# 4axis_DRV8818.net
KiCad netlist of a schematic drawn in EAGLE
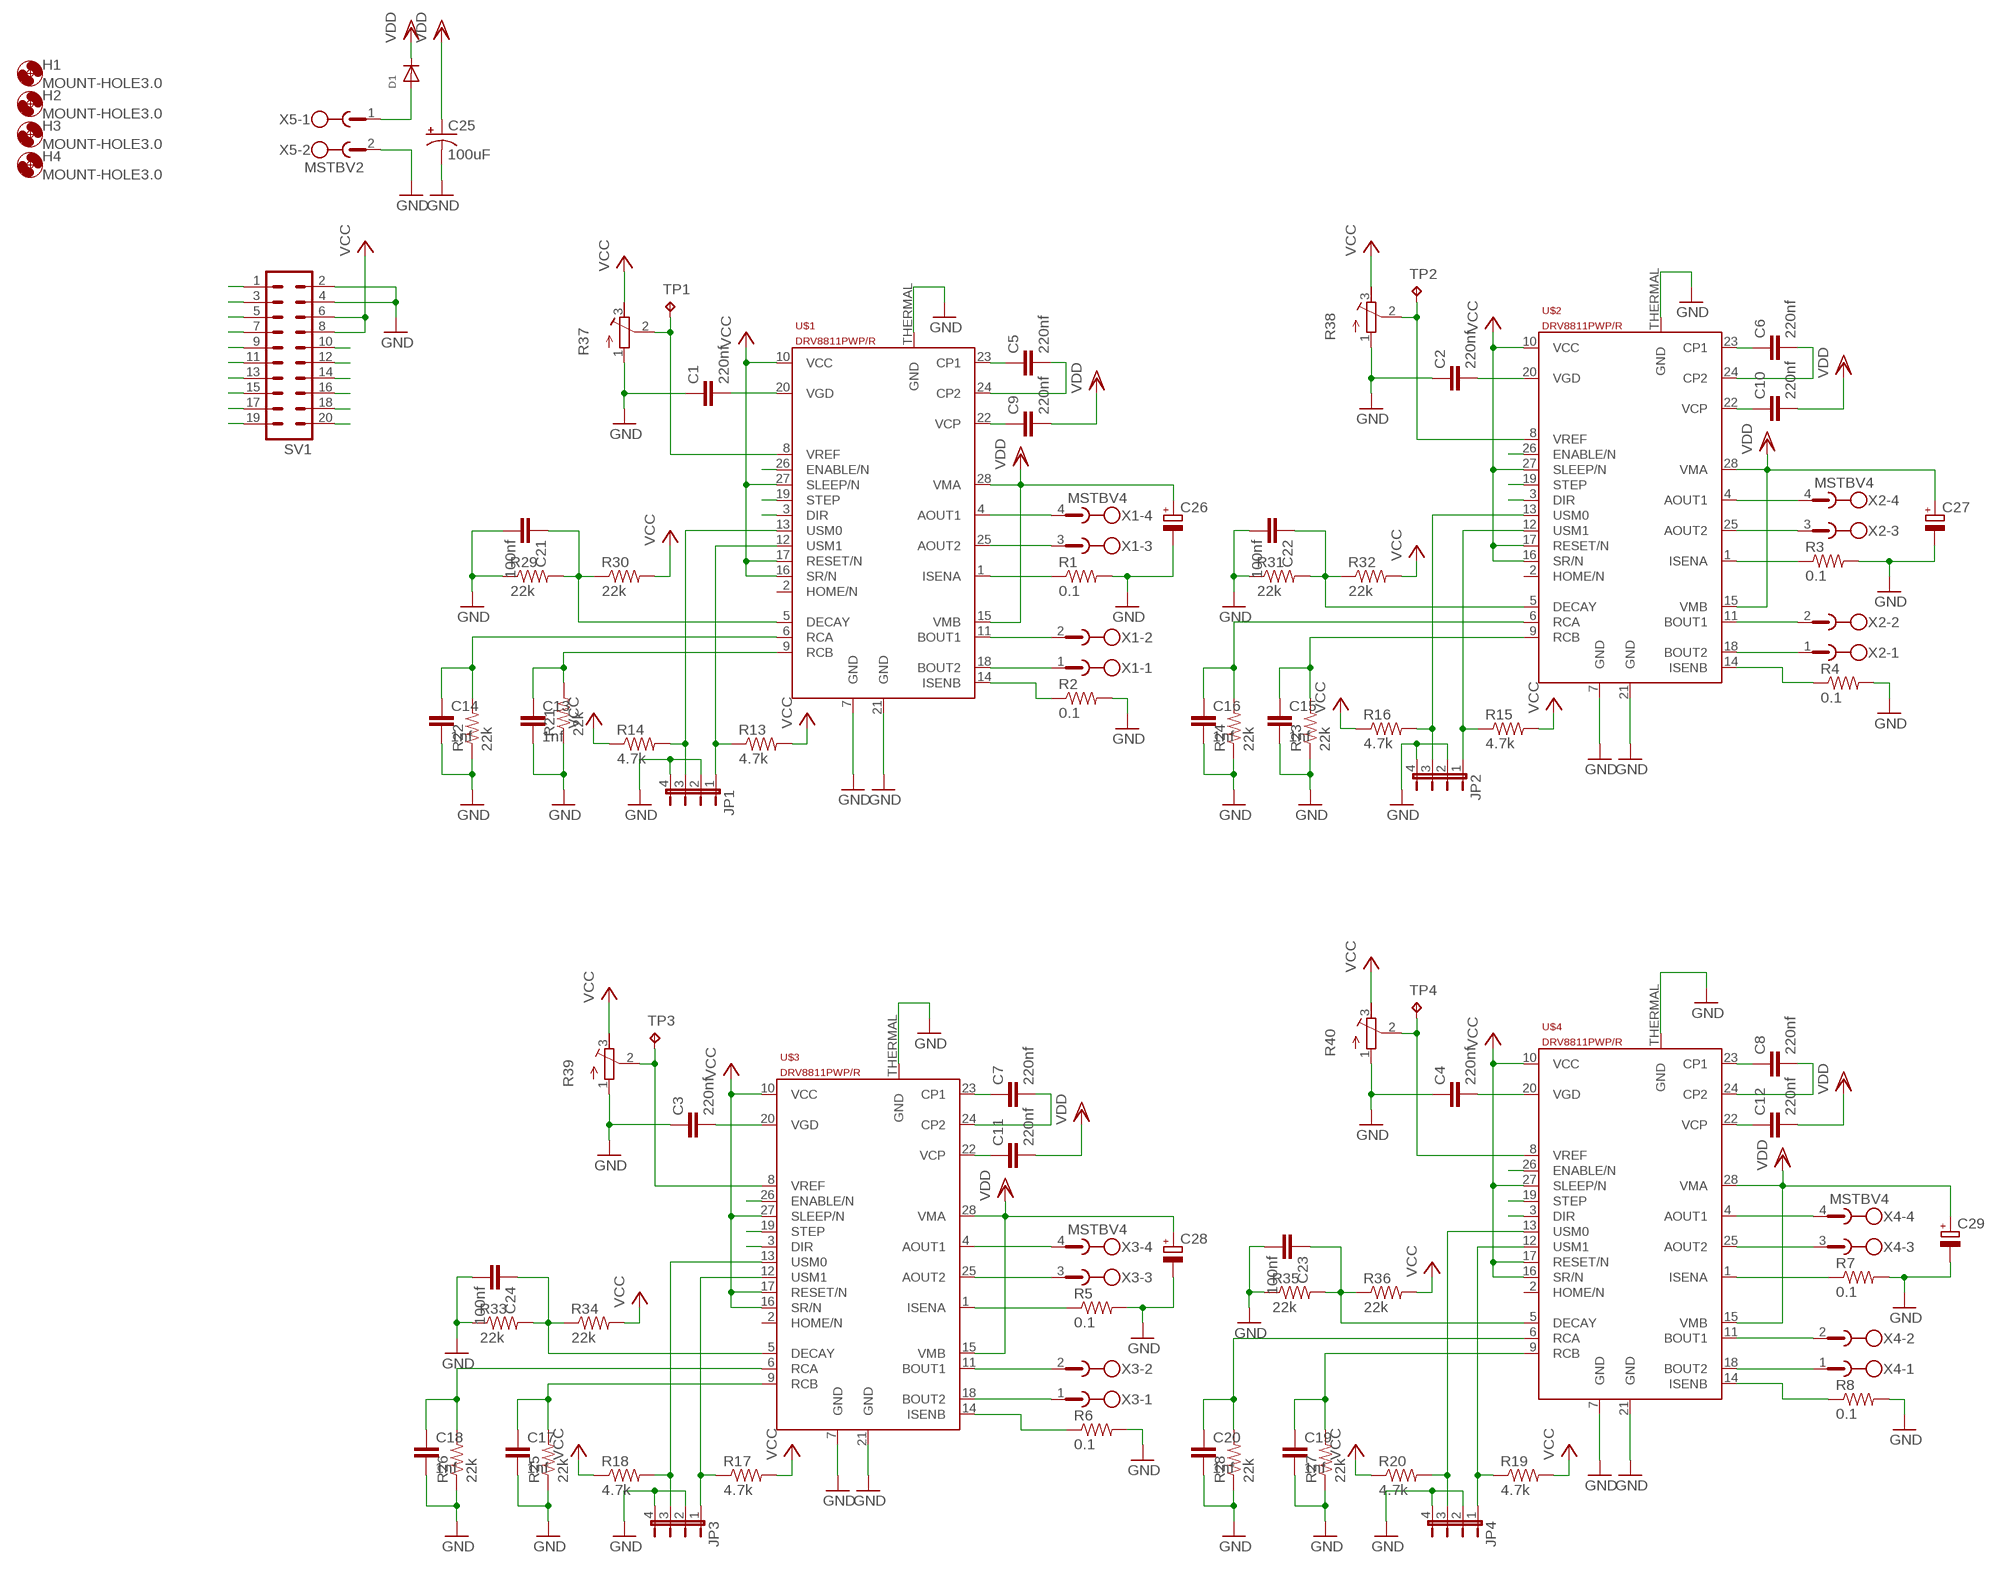
[diagram p0: schematic, sheet 1]

(export (version "E")
  (design (tool "Eeschema 10.0.6"))
  (components
    (comp (ref "C1")
      (value "220nf")
      (footprint "eagle-import:C1206")
      (libsource (lib "eagle-import") (part "C-EUC1206"))
    )
    (comp (ref "C2")
      (value "220nf")
      (footprint "eagle-import:C1206")
      (libsource (lib "eagle-import") (part "C-EUC1206"))
    )
    (comp (ref "C3")
      (value "220nf")
      (footprint "eagle-import:C1206")
      (libsource (lib "eagle-import") (part "C-EUC1206"))
    )
    (comp (ref "C4")
      (value "220nf")
      (footprint "eagle-import:C1206")
      (libsource (lib "eagle-import") (part "C-EUC1206"))
    )
    (comp (ref "C5")
      (value "220nf")
      (footprint "eagle-import:C1206")
      (libsource (lib "eagle-import") (part "C-EUC1206"))
    )
    (comp (ref "C6")
      (value "220nf")
      (footprint "eagle-import:C1206")
      (libsource (lib "eagle-import") (part "C-EUC1206"))
    )
    (comp (ref "C7")
      (value "220nf")
      (footprint "eagle-import:C1206")
      (libsource (lib "eagle-import") (part "C-EUC1206"))
    )
    (comp (ref "C8")
      (value "220nf")
      (footprint "eagle-import:C1206")
      (libsource (lib "eagle-import") (part "C-EUC1206"))
    )
    (comp (ref "C9")
      (value "220nf")
      (footprint "eagle-import:C1206")
      (libsource (lib "eagle-import") (part "C-EUC1206"))
    )
    (comp (ref "C10")
      (value "220nf")
      (footprint "eagle-import:C1206")
      (libsource (lib "eagle-import") (part "C-EUC1206"))
    )
    (comp (ref "C11")
      (value "220nf")
      (footprint "eagle-import:C1206")
      (libsource (lib "eagle-import") (part "C-EUC1206"))
    )
    (comp (ref "C12")
      (value "220nf")
      (footprint "eagle-import:C1206")
      (libsource (lib "eagle-import") (part "C-EUC1206"))
    )
    (comp (ref "C13")
      (value "1nf")
      (footprint "eagle-import:C1206")
      (libsource (lib "eagle-import") (part "C-EUC1206"))
    )
    (comp (ref "C14")
      (value "1nf")
      (footprint "eagle-import:C1206")
      (libsource (lib "eagle-import") (part "C-EUC1206"))
    )
    (comp (ref "C15")
      (value "1nf")
      (footprint "eagle-import:C1206")
      (libsource (lib "eagle-import") (part "C-EUC1206"))
    )
    (comp (ref "C16")
      (value "1nf")
      (footprint "eagle-import:C1206")
      (libsource (lib "eagle-import") (part "C-EUC1206"))
    )
    (comp (ref "C17")
      (value "1nf")
      (footprint "eagle-import:C1206")
      (libsource (lib "eagle-import") (part "C-EUC1206"))
    )
    (comp (ref "C18")
      (value "1nf")
      (footprint "eagle-import:C1206")
      (libsource (lib "eagle-import") (part "C-EUC1206"))
    )
    (comp (ref "C19")
      (value "1nf")
      (footprint "eagle-import:C1206")
      (libsource (lib "eagle-import") (part "C-EUC1206"))
    )
    (comp (ref "C20")
      (value "1nf")
      (footprint "eagle-import:C1206")
      (libsource (lib "eagle-import") (part "C-EUC1206"))
    )
    (comp (ref "C21")
      (value "100nf")
      (footprint "eagle-import:C1206")
      (libsource (lib "eagle-import") (part "C-EUC1206"))
    )
    (comp (ref "C22")
      (value "100nf")
      (footprint "eagle-import:C1206")
      (libsource (lib "eagle-import") (part "C-EUC1206"))
    )
    (comp (ref "C23")
      (value "100nf")
      (footprint "eagle-import:C1206")
      (libsource (lib "eagle-import") (part "C-EUC1206"))
    )
    (comp (ref "C24")
      (value "100nf")
      (footprint "eagle-import:C1206")
      (libsource (lib "eagle-import") (part "C-EUC1206"))
    )
    (comp (ref "C25")
      (value "100uF")
      (footprint "eagle-import:NIC_10X10.5_CAP")
      (libsource (lib "eagle-import") (part "100UF-63V-20%(ELECT)"))
    )
    (comp (ref "C26")
      (value "CPOL-EUD")
      (footprint "eagle-import:PANASONIC_D")
      (libsource (lib "eagle-import") (part "CPOL-EUD"))
    )
    (comp (ref "C27")
      (value "CPOL-EUD")
      (footprint "eagle-import:PANASONIC_D")
      (libsource (lib "eagle-import") (part "CPOL-EUD"))
    )
    (comp (ref "C28")
      (value "CPOL-EUD")
      (footprint "eagle-import:PANASONIC_D")
      (libsource (lib "eagle-import") (part "CPOL-EUD"))
    )
    (comp (ref "C29")
      (value "CPOL-EUD")
      (footprint "eagle-import:PANASONIC_D")
      (libsource (lib "eagle-import") (part "CPOL-EUD"))
    )
    (comp (ref "D1")
      (value "DIODESMA")
      (footprint "eagle-import:SMADIODE")
      (libsource (lib "eagle-import") (part "DIODESMA"))
    )
    (comp (ref "H1")
      (value "MOUNT-HOLE3.0")
      (footprint "eagle-import:3,0")
      (libsource (lib "eagle-import") (part "MOUNT-HOLE3.0"))
    )
    (comp (ref "H2")
      (value "MOUNT-HOLE3.0")
      (footprint "eagle-import:3,0")
      (libsource (lib "eagle-import") (part "MOUNT-HOLE3.0"))
    )
    (comp (ref "H3")
      (value "MOUNT-HOLE3.0")
      (footprint "eagle-import:3,0")
      (libsource (lib "eagle-import") (part "MOUNT-HOLE3.0"))
    )
    (comp (ref "H4")
      (value "MOUNT-HOLE3.0")
      (footprint "eagle-import:3,0")
      (libsource (lib "eagle-import") (part "MOUNT-HOLE3.0"))
    )
    (comp (ref "JP1")
      (value "JP4E")
      (footprint "eagle-import:JP4")
      (libsource (lib "eagle-import") (part "JP4E"))
    )
    (comp (ref "JP2")
      (value "JP4E")
      (footprint "eagle-import:JP4")
      (libsource (lib "eagle-import") (part "JP4E"))
    )
    (comp (ref "JP3")
      (value "JP4E")
      (footprint "eagle-import:JP4")
      (libsource (lib "eagle-import") (part "JP4E"))
    )
    (comp (ref "JP4")
      (value "JP4E")
      (footprint "eagle-import:JP4")
      (libsource (lib "eagle-import") (part "JP4E"))
    )
    (comp (ref "R1")
      (value "0.1")
      (footprint "eagle-import:R2512")
      (libsource (lib "eagle-import") (part "R-US_R2512"))
    )
    (comp (ref "R2")
      (value "0.1")
      (footprint "eagle-import:R2512")
      (libsource (lib "eagle-import") (part "R-US_R2512"))
    )
    (comp (ref "R3")
      (value "0.1")
      (footprint "eagle-import:R2512")
      (libsource (lib "eagle-import") (part "R-US_R2512"))
    )
    (comp (ref "R4")
      (value "0.1")
      (footprint "eagle-import:R2512")
      (libsource (lib "eagle-import") (part "R-US_R2512"))
    )
    (comp (ref "R5")
      (value "0.1")
      (footprint "eagle-import:R2512")
      (libsource (lib "eagle-import") (part "R-US_R2512"))
    )
    (comp (ref "R6")
      (value "0.1")
      (footprint "eagle-import:R2512")
      (libsource (lib "eagle-import") (part "R-US_R2512"))
    )
    (comp (ref "R7")
      (value "0.1")
      (footprint "eagle-import:R2512")
      (libsource (lib "eagle-import") (part "R-US_R2512"))
    )
    (comp (ref "R8")
      (value "0.1")
      (footprint "eagle-import:R2512")
      (libsource (lib "eagle-import") (part "R-US_R2512"))
    )
    (comp (ref "R13")
      (value "4.7k")
      (footprint "eagle-import:R1206")
      (libsource (lib "eagle-import") (part "R-US_R1206"))
    )
    (comp (ref "R14")
      (value "4.7k")
      (footprint "eagle-import:R1206")
      (libsource (lib "eagle-import") (part "R-US_R1206"))
    )
    (comp (ref "R15")
      (value "4.7k")
      (footprint "eagle-import:R1206")
      (libsource (lib "eagle-import") (part "R-US_R1206"))
    )
    (comp (ref "R16")
      (value "4.7k")
      (footprint "eagle-import:R1206")
      (libsource (lib "eagle-import") (part "R-US_R1206"))
    )
    (comp (ref "R17")
      (value "4.7k")
      (footprint "eagle-import:R1206")
      (libsource (lib "eagle-import") (part "R-US_R1206"))
    )
    (comp (ref "R18")
      (value "4.7k")
      (footprint "eagle-import:R1206")
      (libsource (lib "eagle-import") (part "R-US_R1206"))
    )
    (comp (ref "R19")
      (value "4.7k")
      (footprint "eagle-import:R1206")
      (libsource (lib "eagle-import") (part "R-US_R1206"))
    )
    (comp (ref "R20")
      (value "4.7k")
      (footprint "eagle-import:R1206")
      (libsource (lib "eagle-import") (part "R-US_R1206"))
    )
    (comp (ref "R21")
      (value "22k")
      (footprint "eagle-import:R1206")
      (libsource (lib "eagle-import") (part "R-US_R1206"))
    )
    (comp (ref "R22")
      (value "22k")
      (footprint "eagle-import:R1206")
      (libsource (lib "eagle-import") (part "R-US_R1206"))
    )
    (comp (ref "R23")
      (value "22k")
      (footprint "eagle-import:R1206")
      (libsource (lib "eagle-import") (part "R-US_R1206"))
    )
    (comp (ref "R24")
      (value "22k")
      (footprint "eagle-import:R1206")
      (libsource (lib "eagle-import") (part "R-US_R1206"))
    )
    (comp (ref "R25")
      (value "22k")
      (footprint "eagle-import:R1206")
      (libsource (lib "eagle-import") (part "R-US_R1206"))
    )
    (comp (ref "R26")
      (value "22k")
      (footprint "eagle-import:R1206")
      (libsource (lib "eagle-import") (part "R-US_R1206"))
    )
    (comp (ref "R27")
      (value "22k")
      (footprint "eagle-import:R1206")
      (libsource (lib "eagle-import") (part "R-US_R1206"))
    )
    (comp (ref "R28")
      (value "22k")
      (footprint "eagle-import:R1206")
      (libsource (lib "eagle-import") (part "R-US_R1206"))
    )
    (comp (ref "R29")
      (value "22k")
      (footprint "eagle-import:R1206")
      (libsource (lib "eagle-import") (part "R-US_R1206"))
    )
    (comp (ref "R30")
      (value "22k")
      (footprint "eagle-import:R1206")
      (libsource (lib "eagle-import") (part "R-US_R1206"))
    )
    (comp (ref "R31")
      (value "22k")
      (footprint "eagle-import:R1206")
      (libsource (lib "eagle-import") (part "R-US_R1206"))
    )
    (comp (ref "R32")
      (value "22k")
      (footprint "eagle-import:R1206")
      (libsource (lib "eagle-import") (part "R-US_R1206"))
    )
    (comp (ref "R33")
      (value "22k")
      (footprint "eagle-import:R1206")
      (libsource (lib "eagle-import") (part "R-US_R1206"))
    )
    (comp (ref "R34")
      (value "22k")
      (footprint "eagle-import:R1206")
      (libsource (lib "eagle-import") (part "R-US_R1206"))
    )
    (comp (ref "R35")
      (value "22k")
      (footprint "eagle-import:R1206")
      (libsource (lib "eagle-import") (part "R-US_R1206"))
    )
    (comp (ref "R36")
      (value "22k")
      (footprint "eagle-import:R1206")
      (libsource (lib "eagle-import") (part "R-US_R1206"))
    )
    (comp (ref "R37")
      (value "R-TRIMM3103")
      (footprint "eagle-import:RTRIM3103")
      (libsource (lib "eagle-import") (part "R-TRIMM3103"))
    )
    (comp (ref "R38")
      (value "R-TRIMM3103")
      (footprint "eagle-import:RTRIM3103")
      (libsource (lib "eagle-import") (part "R-TRIMM3103"))
    )
    (comp (ref "R39")
      (value "R-TRIMM3103")
      (footprint "eagle-import:RTRIM3103")
      (libsource (lib "eagle-import") (part "R-TRIMM3103"))
    )
    (comp (ref "R40")
      (value "R-TRIMM3103")
      (footprint "eagle-import:RTRIM3103")
      (libsource (lib "eagle-import") (part "R-TRIMM3103"))
    )
    (comp (ref "SV1")
      (value "ML20")
      (footprint "eagle-import:ML20")
      (libsource (lib "eagle-import") (part "ML20"))
    )
    (comp (ref "TP1")
      (value "TPTP20R")
      (footprint "eagle-import:TP20R")
      (libsource (lib "eagle-import") (part "TPTP20R"))
    )
    (comp (ref "TP2")
      (value "TPTP20R")
      (footprint "eagle-import:TP20R")
      (libsource (lib "eagle-import") (part "TPTP20R"))
    )
    (comp (ref "TP3")
      (value "TPTP20R")
      (footprint "eagle-import:TP20R")
      (libsource (lib "eagle-import") (part "TPTP20R"))
    )
    (comp (ref "TP4")
      (value "TPTP20R")
      (footprint "eagle-import:TP20R")
      (libsource (lib "eagle-import") (part "TPTP20R"))
    )
    (comp (ref "U$1")
      (value "DRV8811PWP/R")
      (footprint "eagle-import:HTSSOP28")
      (fields (field (name "MF") "TEXAS INSTRUMENTS"))
      (libsource (lib "eagle-import") (part "DRV8811PWP/R"))
    )
    (comp (ref "U$2")
      (value "DRV8811PWP/R")
      (footprint "eagle-import:HTSSOP28")
      (fields (field (name "MF") "TEXAS INSTRUMENTS"))
      (libsource (lib "eagle-import") (part "DRV8811PWP/R"))
    )
    (comp (ref "U$3")
      (value "DRV8811PWP/R")
      (footprint "eagle-import:HTSSOP28")
      (fields (field (name "MF") "TEXAS INSTRUMENTS"))
      (libsource (lib "eagle-import") (part "DRV8811PWP/R"))
    )
    (comp (ref "U$4")
      (value "DRV8811PWP/R")
      (footprint "eagle-import:HTSSOP28")
      (fields (field (name "MF") "TEXAS INSTRUMENTS"))
      (libsource (lib "eagle-import") (part "DRV8811PWP/R"))
    )
    (comp (ref "X1")
      (value "MSTBV4")
      (footprint "eagle-import:MSTBV4")
      (fields (field (name "MPN") "MSTBV 2,5/4-GF-5.08"))
      (libsource (lib "eagle-import") (part "MSTBV4"))
    )
    (comp (ref "X2")
      (value "MSTBV4")
      (footprint "eagle-import:MSTBV4")
      (fields (field (name "MPN") "MSTBV 2,5/4-GF-5.08"))
      (libsource (lib "eagle-import") (part "MSTBV4"))
    )
    (comp (ref "X3")
      (value "MSTBV4")
      (footprint "eagle-import:MSTBV4")
      (fields (field (name "MPN") "MSTBV 2,5/4-GF-5.08"))
      (libsource (lib "eagle-import") (part "MSTBV4"))
    )
    (comp (ref "X4")
      (value "MSTBV4")
      (footprint "eagle-import:MSTBV4")
      (fields (field (name "MPN") "MSTBV 2,5/4-GF-5.08"))
      (libsource (lib "eagle-import") (part "MSTBV4"))
    )
    (comp (ref "X5")
      (value "MSTBV2")
      (footprint "eagle-import:MSTBV2")
      (fields (field (name "MPN") "MSTBV 2,5/2-GF-5.08"))
      (libsource (lib "eagle-import") (part "MSTBV2"))
    )
  )
  (nets
    (net (code "1") (name "/E-DıR") (class "Default")
      (node (ref "SV1") (pin "14") (pinfunction "14_14") (pintype "passive"))
      (node (ref "U$4") (pin "3") (pinfunction "DIR_3") (pintype "input"))
    )
    (net (code "2") (name "/E-EN") (class "Default")
      (node (ref "SV1") (pin "16") (pinfunction "16_16") (pintype "passive"))
      (node (ref "U$4") (pin "26") (pinfunction "ENABLE/N_26") (pintype "input"))
    )
    (net (code "3") (name "/E-STEP") (class "Default")
      (node (ref "SV1") (pin "12") (pinfunction "12_12") (pintype "passive"))
      (node (ref "U$4") (pin "19") (pinfunction "STEP_19") (pintype "input"))
    )
    (net (code "4") (name "/X-DıR") (class "Default")
      (node (ref "SV1") (pin "3") (pinfunction "3_3") (pintype "passive"))
      (node (ref "U$1") (pin "3") (pinfunction "DIR_3") (pintype "input"))
    )
    (net (code "5") (name "/X-EN") (class "Default")
      (node (ref "SV1") (pin "1") (pinfunction "1_1") (pintype "passive"))
      (node (ref "U$1") (pin "26") (pinfunction "ENABLE/N_26") (pintype "input"))
    )
    (net (code "6") (name "/X-STEP") (class "Default")
      (node (ref "SV1") (pin "5") (pinfunction "5_5") (pintype "passive"))
      (node (ref "U$1") (pin "19") (pinfunction "STEP_19") (pintype "input"))
    )
    (net (code "7") (name "/Y-DıR") (class "Default")
      (node (ref "SV1") (pin "11") (pinfunction "11_11") (pintype "passive"))
      (node (ref "U$2") (pin "3") (pinfunction "DIR_3") (pintype "input"))
    )
    (net (code "8") (name "/Y-EN") (class "Default")
      (node (ref "SV1") (pin "9") (pinfunction "9_9") (pintype "passive"))
      (node (ref "U$2") (pin "26") (pinfunction "ENABLE/N_26") (pintype "input"))
    )
    (net (code "9") (name "/Y-STEP") (class "Default")
      (node (ref "SV1") (pin "13") (pinfunction "13_13") (pintype "passive"))
      (node (ref "U$2") (pin "19") (pinfunction "STEP_19") (pintype "input"))
    )
    (net (code "10") (name "/Z-DıR") (class "Default")
      (node (ref "SV1") (pin "19") (pinfunction "19_19") (pintype "passive"))
      (node (ref "U$3") (pin "3") (pinfunction "DIR_3") (pintype "input"))
    )
    (net (code "11") (name "/Z-EN") (class "Default")
      (node (ref "SV1") (pin "17") (pinfunction "17_17") (pintype "passive"))
      (node (ref "U$3") (pin "26") (pinfunction "ENABLE/N_26") (pintype "input"))
    )
    (net (code "12") (name "/Z-STEP") (class "Default")
      (node (ref "SV1") (pin "20") (pinfunction "20_20") (pintype "passive"))
      (node (ref "U$3") (pin "19") (pinfunction "STEP_19") (pintype "input"))
    )
    (net (code "13") (name "GND") (class "Default")
      (node (ref "C1") (pin "1") (pinfunction "1_1") (pintype "passive"))
      (node (ref "C13") (pin "2") (pinfunction "2_2") (pintype "passive"))
      (node (ref "C14") (pin "2") (pinfunction "2_2") (pintype "passive"))
      (node (ref "C15") (pin "2") (pinfunction "2_2") (pintype "passive"))
      (node (ref "C16") (pin "2") (pinfunction "2_2") (pintype "passive"))
      (node (ref "C17") (pin "2") (pinfunction "2_2") (pintype "passive"))
      (node (ref "C18") (pin "2") (pinfunction "2_2") (pintype "passive"))
      (node (ref "C19") (pin "2") (pinfunction "2_2") (pintype "passive"))
      (node (ref "C2") (pin "1") (pinfunction "1_1") (pintype "passive"))
      (node (ref "C20") (pin "2") (pinfunction "2_2") (pintype "passive"))
      (node (ref "C21") (pin "2") (pinfunction "2_2") (pintype "passive"))
      (node (ref "C22") (pin "2") (pinfunction "2_2") (pintype "passive"))
      (node (ref "C23") (pin "2") (pinfunction "2_2") (pintype "passive"))
      (node (ref "C24") (pin "2") (pinfunction "2_2") (pintype "passive"))
      (node (ref "C25") (pin "-") (pinfunction "-_-") (pintype "passive"))
      (node (ref "C26") (pin "-") (pinfunction "-_-") (pintype "passive"))
      (node (ref "C27") (pin "-") (pinfunction "-_-") (pintype "passive"))
      (node (ref "C28") (pin "-") (pinfunction "-_-") (pintype "passive"))
      (node (ref "C29") (pin "-") (pinfunction "-_-") (pintype "passive"))
      (node (ref "C3") (pin "1") (pinfunction "1_1") (pintype "passive"))
      (node (ref "C4") (pin "1") (pinfunction "1_1") (pintype "passive"))
      (node (ref "JP1") (pin "2") (pinfunction "2_2") (pintype "passive"))
      (node (ref "JP1") (pin "4") (pinfunction "4_4") (pintype "passive"))
      (node (ref "JP2") (pin "2") (pinfunction "2_2") (pintype "passive"))
      (node (ref "JP2") (pin "4") (pinfunction "4_4") (pintype "passive"))
      (node (ref "JP3") (pin "2") (pinfunction "2_2") (pintype "passive"))
      (node (ref "JP3") (pin "4") (pinfunction "4_4") (pintype "passive"))
      (node (ref "JP4") (pin "2") (pinfunction "2_2") (pintype "passive"))
      (node (ref "JP4") (pin "4") (pinfunction "4_4") (pintype "passive"))
      (node (ref "R1") (pin "2") (pinfunction "2_2") (pintype "passive"))
      (node (ref "R2") (pin "2") (pinfunction "2_2") (pintype "passive"))
      (node (ref "R21") (pin "1") (pinfunction "1_1") (pintype "passive"))
      (node (ref "R22") (pin "1") (pinfunction "1_1") (pintype "passive"))
      (node (ref "R23") (pin "1") (pinfunction "1_1") (pintype "passive"))
      (node (ref "R24") (pin "1") (pinfunction "1_1") (pintype "passive"))
      (node (ref "R25") (pin "1") (pinfunction "1_1") (pintype "passive"))
      (node (ref "R26") (pin "1") (pinfunction "1_1") (pintype "passive"))
      (node (ref "R27") (pin "1") (pinfunction "1_1") (pintype "passive"))
      (node (ref "R28") (pin "1") (pinfunction "1_1") (pintype "passive"))
      (node (ref "R29") (pin "1") (pinfunction "1_1") (pintype "passive"))
      (node (ref "R3") (pin "2") (pinfunction "2_2") (pintype "passive"))
      (node (ref "R31") (pin "1") (pinfunction "1_1") (pintype "passive"))
      (node (ref "R33") (pin "1") (pinfunction "1_1") (pintype "passive"))
      (node (ref "R35") (pin "1") (pinfunction "1_1") (pintype "passive"))
      (node (ref "R37") (pin "1") (pinfunction "A_1") (pintype "passive"))
      (node (ref "R38") (pin "1") (pinfunction "A_1") (pintype "passive"))
      (node (ref "R39") (pin "1") (pinfunction "A_1") (pintype "passive"))
      (node (ref "R4") (pin "2") (pinfunction "2_2") (pintype "passive"))
      (node (ref "R40") (pin "1") (pinfunction "A_1") (pintype "passive"))
      (node (ref "R5") (pin "2") (pinfunction "2_2") (pintype "passive"))
      (node (ref "R6") (pin "2") (pinfunction "2_2") (pintype "passive"))
      (node (ref "R7") (pin "2") (pinfunction "2_2") (pintype "passive"))
      (node (ref "R8") (pin "2") (pinfunction "2_2") (pintype "passive"))
      (node (ref "SV1") (pin "2") (pinfunction "2_2") (pintype "passive"))
      (node (ref "SV1") (pin "4") (pinfunction "4_4") (pintype "passive"))
      (node (ref "U$1") (pin "21") (pinfunction "GND_21") (pintype "power_in"))
      (node (ref "U$1") (pin "7") (pinfunction "GND_7") (pintype "power_in"))
      (node (ref "U$1") (pin "THERMAL") (pinfunction "GND_THERMAL") (pintype "power_in"))
      (node (ref "U$2") (pin "21") (pinfunction "GND_21") (pintype "power_in"))
      (node (ref "U$2") (pin "7") (pinfunction "GND_7") (pintype "power_in"))
      (node (ref "U$2") (pin "THERMAL") (pinfunction "GND_THERMAL") (pintype "power_in"))
      (node (ref "U$3") (pin "21") (pinfunction "GND_21") (pintype "power_in"))
      (node (ref "U$3") (pin "7") (pinfunction "GND_7") (pintype "power_in"))
      (node (ref "U$3") (pin "THERMAL") (pinfunction "GND_THERMAL") (pintype "power_in"))
      (node (ref "U$4") (pin "21") (pinfunction "GND_21") (pintype "power_in"))
      (node (ref "U$4") (pin "7") (pinfunction "GND_7") (pintype "power_in"))
      (node (ref "U$4") (pin "THERMAL") (pinfunction "GND_THERMAL") (pintype "power_in"))
      (node (ref "X5") (pin "2") (pinfunction "1_2") (pintype "passive"))
    )
    (net (code "14") (name "Net-(D1-PadA)") (class "Default")
      (node (ref "D1") (pin "A") (pinfunction "A_A") (pintype "passive"))
      (node (ref "X5") (pin "1") (pinfunction "1_1") (pintype "passive"))
    )
    (net (code "15") (name "Net-(R37-S)") (class "Default")
      (node (ref "R37") (pin "2") (pinfunction "S_2") (pintype "passive"))
      (node (ref "TP1") (pin "TP") (pinfunction "TP_TP") (pintype "input"))
      (node (ref "U$1") (pin "8") (pinfunction "VREF_8") (pintype "input"))
    )
    (net (code "16") (name "Net-(R38-S)") (class "Default")
      (node (ref "R38") (pin "2") (pinfunction "S_2") (pintype "passive"))
      (node (ref "TP2") (pin "TP") (pinfunction "TP_TP") (pintype "input"))
      (node (ref "U$2") (pin "8") (pinfunction "VREF_8") (pintype "input"))
    )
    (net (code "17") (name "Net-(R39-S)") (class "Default")
      (node (ref "R39") (pin "2") (pinfunction "S_2") (pintype "passive"))
      (node (ref "TP3") (pin "TP") (pinfunction "TP_TP") (pintype "input"))
      (node (ref "U$3") (pin "8") (pinfunction "VREF_8") (pintype "input"))
    )
    (net (code "18") (name "Net-(R40-S)") (class "Default")
      (node (ref "R40") (pin "2") (pinfunction "S_2") (pintype "passive"))
      (node (ref "TP4") (pin "TP") (pinfunction "TP_TP") (pintype "input"))
      (node (ref "U$4") (pin "8") (pinfunction "VREF_8") (pintype "input"))
    )
    (net (code "19") (name "Net-(U$1-AOUT1)") (class "Default")
      (node (ref "U$1") (pin "4") (pinfunction "AOUT1_4") (pintype "output"))
      (node (ref "X1") (pin "4") (pinfunction "1_4") (pintype "passive"))
    )
    (net (code "20") (name "Net-(U$1-AOUT2)") (class "Default")
      (node (ref "U$1") (pin "25") (pinfunction "AOUT2_25") (pintype "output"))
      (node (ref "X1") (pin "3") (pinfunction "1_3") (pintype "passive"))
    )
    (net (code "21") (name "Net-(U$1-BOUT1)") (class "Default")
      (node (ref "U$1") (pin "11") (pinfunction "BOUT1_11") (pintype "output"))
      (node (ref "X1") (pin "2") (pinfunction "1_2") (pintype "passive"))
    )
    (net (code "22") (name "Net-(U$1-BOUT2)") (class "Default")
      (node (ref "U$1") (pin "18") (pinfunction "BOUT2_18") (pintype "output"))
      (node (ref "X1") (pin "1") (pinfunction "1_1") (pintype "passive"))
    )
    (net (code "23") (name "Net-(U$1-CP1)") (class "Default")
      (node (ref "C5") (pin "1") (pinfunction "1_1") (pintype "passive"))
      (node (ref "U$1") (pin "23") (pinfunction "CP1_23") (pintype "bidirectional"))
    )
    (net (code "24") (name "Net-(U$1-CP2)") (class "Default")
      (node (ref "C5") (pin "2") (pinfunction "2_2") (pintype "passive"))
      (node (ref "U$1") (pin "24") (pinfunction "CP2_24") (pintype "bidirectional"))
    )
    (net (code "25") (name "Net-(U$1-DECAY)") (class "Default")
      (node (ref "C21") (pin "1") (pinfunction "1_1") (pintype "passive"))
      (node (ref "R29") (pin "2") (pinfunction "2_2") (pintype "passive"))
      (node (ref "R30") (pin "1") (pinfunction "1_1") (pintype "passive"))
      (node (ref "U$1") (pin "5") (pinfunction "DECAY_5") (pintype "input"))
    )
    (net (code "26") (name "Net-(U$1-ISENA)") (class "Default")
      (node (ref "R1") (pin "1") (pinfunction "1_1") (pintype "passive"))
      (node (ref "U$1") (pin "1") (pinfunction "ISENA_1") (pintype "power_in"))
    )
    (net (code "27") (name "Net-(U$1-ISENB)") (class "Default")
      (node (ref "R2") (pin "1") (pinfunction "1_1") (pintype "passive"))
      (node (ref "U$1") (pin "14") (pinfunction "ISENB_14") (pintype "power_in"))
    )
    (net (code "28") (name "Net-(U$1-RCA)") (class "Default")
      (node (ref "C14") (pin "1") (pinfunction "1_1") (pintype "passive"))
      (node (ref "R22") (pin "2") (pinfunction "2_2") (pintype "passive"))
      (node (ref "U$1") (pin "6") (pinfunction "RCA_6") (pintype "input"))
    )
    (net (code "29") (name "Net-(U$1-RCB)") (class "Default")
      (node (ref "C13") (pin "1") (pinfunction "1_1") (pintype "passive"))
      (node (ref "R21") (pin "2") (pinfunction "2_2") (pintype "passive"))
      (node (ref "U$1") (pin "9") (pinfunction "RCB_9") (pintype "input"))
    )
    (net (code "30") (name "Net-(U$1-USM0)") (class "Default")
      (node (ref "JP1") (pin "3") (pinfunction "3_3") (pintype "passive"))
      (node (ref "R14") (pin "2") (pinfunction "2_2") (pintype "passive"))
      (node (ref "U$1") (pin "13") (pinfunction "USM0_13") (pintype "input"))
    )
    (net (code "31") (name "Net-(U$1-USM1)") (class "Default")
      (node (ref "JP1") (pin "1") (pinfunction "1_1") (pintype "passive"))
      (node (ref "R13") (pin "1") (pinfunction "1_1") (pintype "passive"))
      (node (ref "U$1") (pin "12") (pinfunction "USM1_12") (pintype "input"))
    )
    (net (code "32") (name "Net-(U$1-VCP)") (class "Default")
      (node (ref "C9") (pin "1") (pinfunction "1_1") (pintype "passive"))
      (node (ref "U$1") (pin "22") (pinfunction "VCP_22") (pintype "bidirectional"))
    )
    (net (code "33") (name "Net-(U$1-VGD)") (class "Default")
      (node (ref "C1") (pin "2") (pinfunction "2_2") (pintype "passive"))
      (node (ref "U$1") (pin "20") (pinfunction "VGD_20") (pintype "bidirectional"))
    )
    (net (code "34") (name "Net-(U$2-AOUT1)") (class "Default")
      (node (ref "U$2") (pin "4") (pinfunction "AOUT1_4") (pintype "output"))
      (node (ref "X2") (pin "4") (pinfunction "1_4") (pintype "passive"))
    )
    (net (code "35") (name "Net-(U$2-AOUT2)") (class "Default")
      (node (ref "U$2") (pin "25") (pinfunction "AOUT2_25") (pintype "output"))
      (node (ref "X2") (pin "3") (pinfunction "1_3") (pintype "passive"))
    )
    (net (code "36") (name "Net-(U$2-BOUT1)") (class "Default")
      (node (ref "U$2") (pin "11") (pinfunction "BOUT1_11") (pintype "output"))
      (node (ref "X2") (pin "2") (pinfunction "1_2") (pintype "passive"))
    )
    (net (code "37") (name "Net-(U$2-BOUT2)") (class "Default")
      (node (ref "U$2") (pin "18") (pinfunction "BOUT2_18") (pintype "output"))
      (node (ref "X2") (pin "1") (pinfunction "1_1") (pintype "passive"))
    )
    (net (code "38") (name "Net-(U$2-CP1)") (class "Default")
      (node (ref "C6") (pin "1") (pinfunction "1_1") (pintype "passive"))
      (node (ref "U$2") (pin "23") (pinfunction "CP1_23") (pintype "bidirectional"))
    )
    (net (code "39") (name "Net-(U$2-CP2)") (class "Default")
      (node (ref "C6") (pin "2") (pinfunction "2_2") (pintype "passive"))
      (node (ref "U$2") (pin "24") (pinfunction "CP2_24") (pintype "bidirectional"))
    )
    (net (code "40") (name "Net-(U$2-DECAY)") (class "Default")
      (node (ref "C22") (pin "1") (pinfunction "1_1") (pintype "passive"))
      (node (ref "R31") (pin "2") (pinfunction "2_2") (pintype "passive"))
      (node (ref "R32") (pin "1") (pinfunction "1_1") (pintype "passive"))
      (node (ref "U$2") (pin "5") (pinfunction "DECAY_5") (pintype "input"))
    )
    (net (code "41") (name "Net-(U$2-ISENA)") (class "Default")
      (node (ref "R3") (pin "1") (pinfunction "1_1") (pintype "passive"))
      (node (ref "U$2") (pin "1") (pinfunction "ISENA_1") (pintype "power_in"))
    )
    (net (code "42") (name "Net-(U$2-ISENB)") (class "Default")
      (node (ref "R4") (pin "1") (pinfunction "1_1") (pintype "passive"))
      (node (ref "U$2") (pin "14") (pinfunction "ISENB_14") (pintype "power_in"))
    )
    (net (code "43") (name "Net-(U$2-RCA)") (class "Default")
      (node (ref "C16") (pin "1") (pinfunction "1_1") (pintype "passive"))
      (node (ref "R24") (pin "2") (pinfunction "2_2") (pintype "passive"))
      (node (ref "U$2") (pin "6") (pinfunction "RCA_6") (pintype "input"))
    )
    (net (code "44") (name "Net-(U$2-RCB)") (class "Default")
      (node (ref "C15") (pin "1") (pinfunction "1_1") (pintype "passive"))
      (node (ref "R23") (pin "2") (pinfunction "2_2") (pintype "passive"))
      (node (ref "U$2") (pin "9") (pinfunction "RCB_9") (pintype "input"))
    )
    (net (code "45") (name "Net-(U$2-USM0)") (class "Default")
      (node (ref "JP2") (pin "3") (pinfunction "3_3") (pintype "passive"))
      (node (ref "R16") (pin "2") (pinfunction "2_2") (pintype "passive"))
      (node (ref "U$2") (pin "13") (pinfunction "USM0_13") (pintype "input"))
    )
    (net (code "46") (name "Net-(U$2-USM1)") (class "Default")
      (node (ref "JP2") (pin "1") (pinfunction "1_1") (pintype "passive"))
      (node (ref "R15") (pin "1") (pinfunction "1_1") (pintype "passive"))
      (node (ref "U$2") (pin "12") (pinfunction "USM1_12") (pintype "input"))
    )
    (net (code "47") (name "Net-(U$2-VCP)") (class "Default")
      (node (ref "C10") (pin "1") (pinfunction "1_1") (pintype "passive"))
      (node (ref "U$2") (pin "22") (pinfunction "VCP_22") (pintype "bidirectional"))
    )
    (net (code "48") (name "Net-(U$2-VGD)") (class "Default")
      (node (ref "C2") (pin "2") (pinfunction "2_2") (pintype "passive"))
      (node (ref "U$2") (pin "20") (pinfunction "VGD_20") (pintype "bidirectional"))
    )
    (net (code "49") (name "Net-(U$3-AOUT1)") (class "Default")
      (node (ref "U$3") (pin "4") (pinfunction "AOUT1_4") (pintype "output"))
      (node (ref "X3") (pin "4") (pinfunction "1_4") (pintype "passive"))
    )
    (net (code "50") (name "Net-(U$3-AOUT2)") (class "Default")
      (node (ref "U$3") (pin "25") (pinfunction "AOUT2_25") (pintype "output"))
      (node (ref "X3") (pin "3") (pinfunction "1_3") (pintype "passive"))
    )
    (net (code "51") (name "Net-(U$3-BOUT1)") (class "Default")
      (node (ref "U$3") (pin "11") (pinfunction "BOUT1_11") (pintype "output"))
      (node (ref "X3") (pin "2") (pinfunction "1_2") (pintype "passive"))
    )
    (net (code "52") (name "Net-(U$3-BOUT2)") (class "Default")
      (node (ref "U$3") (pin "18") (pinfunction "BOUT2_18") (pintype "output"))
      (node (ref "X3") (pin "1") (pinfunction "1_1") (pintype "passive"))
    )
    (net (code "53") (name "Net-(U$3-CP1)") (class "Default")
      (node (ref "C7") (pin "1") (pinfunction "1_1") (pintype "passive"))
      (node (ref "U$3") (pin "23") (pinfunction "CP1_23") (pintype "bidirectional"))
    )
    (net (code "54") (name "Net-(U$3-CP2)") (class "Default")
      (node (ref "C7") (pin "2") (pinfunction "2_2") (pintype "passive"))
      (node (ref "U$3") (pin "24") (pinfunction "CP2_24") (pintype "bidirectional"))
    )
    (net (code "55") (name "Net-(U$3-DECAY)") (class "Default")
      (node (ref "C24") (pin "1") (pinfunction "1_1") (pintype "passive"))
      (node (ref "R33") (pin "2") (pinfunction "2_2") (pintype "passive"))
      (node (ref "R34") (pin "1") (pinfunction "1_1") (pintype "passive"))
      (node (ref "U$3") (pin "5") (pinfunction "DECAY_5") (pintype "input"))
    )
    (net (code "56") (name "Net-(U$3-ISENA)") (class "Default")
      (node (ref "R5") (pin "1") (pinfunction "1_1") (pintype "passive"))
      (node (ref "U$3") (pin "1") (pinfunction "ISENA_1") (pintype "power_in"))
    )
    (net (code "57") (name "Net-(U$3-ISENB)") (class "Default")
      (node (ref "R6") (pin "1") (pinfunction "1_1") (pintype "passive"))
      (node (ref "U$3") (pin "14") (pinfunction "ISENB_14") (pintype "power_in"))
    )
    (net (code "58") (name "Net-(U$3-RCA)") (class "Default")
      (node (ref "C18") (pin "1") (pinfunction "1_1") (pintype "passive"))
      (node (ref "R26") (pin "2") (pinfunction "2_2") (pintype "passive"))
      (node (ref "U$3") (pin "6") (pinfunction "RCA_6") (pintype "input"))
    )
    (net (code "59") (name "Net-(U$3-RCB)") (class "Default")
      (node (ref "C17") (pin "1") (pinfunction "1_1") (pintype "passive"))
      (node (ref "R25") (pin "2") (pinfunction "2_2") (pintype "passive"))
      (node (ref "U$3") (pin "9") (pinfunction "RCB_9") (pintype "input"))
    )
    (net (code "60") (name "Net-(U$3-USM0)") (class "Default")
      (node (ref "JP3") (pin "3") (pinfunction "3_3") (pintype "passive"))
      (node (ref "R18") (pin "2") (pinfunction "2_2") (pintype "passive"))
      (node (ref "U$3") (pin "13") (pinfunction "USM0_13") (pintype "input"))
    )
    (net (code "61") (name "Net-(U$3-USM1)") (class "Default")
      (node (ref "JP3") (pin "1") (pinfunction "1_1") (pintype "passive"))
      (node (ref "R17") (pin "1") (pinfunction "1_1") (pintype "passive"))
      (node (ref "U$3") (pin "12") (pinfunction "USM1_12") (pintype "input"))
    )
    (net (code "62") (name "Net-(U$3-VCP)") (class "Default")
      (node (ref "C11") (pin "1") (pinfunction "1_1") (pintype "passive"))
      (node (ref "U$3") (pin "22") (pinfunction "VCP_22") (pintype "bidirectional"))
    )
    (net (code "63") (name "Net-(U$3-VGD)") (class "Default")
      (node (ref "C3") (pin "2") (pinfunction "2_2") (pintype "passive"))
      (node (ref "U$3") (pin "20") (pinfunction "VGD_20") (pintype "bidirectional"))
    )
    (net (code "64") (name "Net-(U$4-AOUT1)") (class "Default")
      (node (ref "U$4") (pin "4") (pinfunction "AOUT1_4") (pintype "output"))
      (node (ref "X4") (pin "4") (pinfunction "1_4") (pintype "passive"))
    )
    (net (code "65") (name "Net-(U$4-AOUT2)") (class "Default")
      (node (ref "U$4") (pin "25") (pinfunction "AOUT2_25") (pintype "output"))
      (node (ref "X4") (pin "3") (pinfunction "1_3") (pintype "passive"))
    )
    (net (code "66") (name "Net-(U$4-BOUT1)") (class "Default")
      (node (ref "U$4") (pin "11") (pinfunction "BOUT1_11") (pintype "output"))
      (node (ref "X4") (pin "2") (pinfunction "1_2") (pintype "passive"))
    )
    (net (code "67") (name "Net-(U$4-BOUT2)") (class "Default")
      (node (ref "U$4") (pin "18") (pinfunction "BOUT2_18") (pintype "output"))
      (node (ref "X4") (pin "1") (pinfunction "1_1") (pintype "passive"))
    )
    (net (code "68") (name "Net-(U$4-CP1)") (class "Default")
      (node (ref "C8") (pin "1") (pinfunction "1_1") (pintype "passive"))
      (node (ref "U$4") (pin "23") (pinfunction "CP1_23") (pintype "bidirectional"))
    )
    (net (code "69") (name "Net-(U$4-CP2)") (class "Default")
      (node (ref "C8") (pin "2") (pinfunction "2_2") (pintype "passive"))
      (node (ref "U$4") (pin "24") (pinfunction "CP2_24") (pintype "bidirectional"))
    )
    (net (code "70") (name "Net-(U$4-DECAY)") (class "Default")
      (node (ref "C23") (pin "1") (pinfunction "1_1") (pintype "passive"))
      (node (ref "R35") (pin "2") (pinfunction "2_2") (pintype "passive"))
      (node (ref "R36") (pin "1") (pinfunction "1_1") (pintype "passive"))
      (node (ref "U$4") (pin "5") (pinfunction "DECAY_5") (pintype "input"))
    )
    (net (code "71") (name "Net-(U$4-ISENA)") (class "Default")
      (node (ref "R7") (pin "1") (pinfunction "1_1") (pintype "passive"))
      (node (ref "U$4") (pin "1") (pinfunction "ISENA_1") (pintype "power_in"))
    )
    (net (code "72") (name "Net-(U$4-ISENB)") (class "Default")
      (node (ref "R8") (pin "1") (pinfunction "1_1") (pintype "passive"))
      (node (ref "U$4") (pin "14") (pinfunction "ISENB_14") (pintype "power_in"))
    )
    (net (code "73") (name "Net-(U$4-RCA)") (class "Default")
      (node (ref "C20") (pin "1") (pinfunction "1_1") (pintype "passive"))
      (node (ref "R28") (pin "2") (pinfunction "2_2") (pintype "passive"))
      (node (ref "U$4") (pin "6") (pinfunction "RCA_6") (pintype "input"))
    )
    (net (code "74") (name "Net-(U$4-RCB)") (class "Default")
      (node (ref "C19") (pin "1") (pinfunction "1_1") (pintype "passive"))
      (node (ref "R27") (pin "2") (pinfunction "2_2") (pintype "passive"))
      (node (ref "U$4") (pin "9") (pinfunction "RCB_9") (pintype "input"))
    )
    (net (code "75") (name "Net-(U$4-USM0)") (class "Default")
      (node (ref "JP4") (pin "3") (pinfunction "3_3") (pintype "passive"))
      (node (ref "R20") (pin "2") (pinfunction "2_2") (pintype "passive"))
      (node (ref "U$4") (pin "13") (pinfunction "USM0_13") (pintype "input"))
    )
    (net (code "76") (name "Net-(U$4-USM1)") (class "Default")
      (node (ref "JP4") (pin "1") (pinfunction "1_1") (pintype "passive"))
      (node (ref "R19") (pin "1") (pinfunction "1_1") (pintype "passive"))
      (node (ref "U$4") (pin "12") (pinfunction "USM1_12") (pintype "input"))
    )
    (net (code "77") (name "Net-(U$4-VCP)") (class "Default")
      (node (ref "C12") (pin "1") (pinfunction "1_1") (pintype "passive"))
      (node (ref "U$4") (pin "22") (pinfunction "VCP_22") (pintype "bidirectional"))
    )
    (net (code "78") (name "Net-(U$4-VGD)") (class "Default")
      (node (ref "C4") (pin "2") (pinfunction "2_2") (pintype "passive"))
      (node (ref "U$4") (pin "20") (pinfunction "VGD_20") (pintype "bidirectional"))
    )
    (net (code "79") (name "VCC") (class "Default")
      (node (ref "R13") (pin "2") (pinfunction "2_2") (pintype "passive"))
      (node (ref "R14") (pin "1") (pinfunction "1_1") (pintype "passive"))
      (node (ref "R15") (pin "2") (pinfunction "2_2") (pintype "passive"))
      (node (ref "R16") (pin "1") (pinfunction "1_1") (pintype "passive"))
      (node (ref "R17") (pin "2") (pinfunction "2_2") (pintype "passive"))
      (node (ref "R18") (pin "1") (pinfunction "1_1") (pintype "passive"))
      (node (ref "R19") (pin "2") (pinfunction "2_2") (pintype "passive"))
      (node (ref "R20") (pin "1") (pinfunction "1_1") (pintype "passive"))
      (node (ref "R30") (pin "2") (pinfunction "2_2") (pintype "passive"))
      (node (ref "R32") (pin "2") (pinfunction "2_2") (pintype "passive"))
      (node (ref "R34") (pin "2") (pinfunction "2_2") (pintype "passive"))
      (node (ref "R36") (pin "2") (pinfunction "2_2") (pintype "passive"))
      (node (ref "R37") (pin "3") (pinfunction "E_3") (pintype "passive"))
      (node (ref "R38") (pin "3") (pinfunction "E_3") (pintype "passive"))
      (node (ref "R39") (pin "3") (pinfunction "E_3") (pintype "passive"))
      (node (ref "R40") (pin "3") (pinfunction "E_3") (pintype "passive"))
      (node (ref "SV1") (pin "6") (pinfunction "6_6") (pintype "passive"))
      (node (ref "SV1") (pin "8") (pinfunction "8_8") (pintype "passive"))
      (node (ref "U$1") (pin "10") (pinfunction "VCC_10") (pintype "power_in"))
      (node (ref "U$1") (pin "16") (pinfunction "SR/N_16") (pintype "input"))
      (node (ref "U$1") (pin "17") (pinfunction "RESET/N_17") (pintype "input"))
      (node (ref "U$1") (pin "27") (pinfunction "SLEEP/N_27") (pintype "input"))
      (node (ref "U$2") (pin "10") (pinfunction "VCC_10") (pintype "power_in"))
      (node (ref "U$2") (pin "16") (pinfunction "SR/N_16") (pintype "input"))
      (node (ref "U$2") (pin "17") (pinfunction "RESET/N_17") (pintype "input"))
      (node (ref "U$2") (pin "27") (pinfunction "SLEEP/N_27") (pintype "input"))
      (node (ref "U$3") (pin "10") (pinfunction "VCC_10") (pintype "power_in"))
      (node (ref "U$3") (pin "16") (pinfunction "SR/N_16") (pintype "input"))
      (node (ref "U$3") (pin "17") (pinfunction "RESET/N_17") (pintype "input"))
      (node (ref "U$3") (pin "27") (pinfunction "SLEEP/N_27") (pintype "input"))
      (node (ref "U$4") (pin "10") (pinfunction "VCC_10") (pintype "power_in"))
      (node (ref "U$4") (pin "16") (pinfunction "SR/N_16") (pintype "input"))
      (node (ref "U$4") (pin "17") (pinfunction "RESET/N_17") (pintype "input"))
      (node (ref "U$4") (pin "27") (pinfunction "SLEEP/N_27") (pintype "input"))
    )
    (net (code "80") (name "VDD") (class "Default")
      (node (ref "C10") (pin "2") (pinfunction "2_2") (pintype "passive"))
      (node (ref "C11") (pin "2") (pinfunction "2_2") (pintype "passive"))
      (node (ref "C12") (pin "2") (pinfunction "2_2") (pintype "passive"))
      (node (ref "C25") (pin "+") (pinfunction "+_+") (pintype "passive"))
      (node (ref "C26") (pin "+") (pinfunction "+_+") (pintype "passive"))
      (node (ref "C27") (pin "+") (pinfunction "+_+") (pintype "passive"))
      (node (ref "C28") (pin "+") (pinfunction "+_+") (pintype "passive"))
      (node (ref "C29") (pin "+") (pinfunction "+_+") (pintype "passive"))
      (node (ref "C9") (pin "2") (pinfunction "2_2") (pintype "passive"))
      (node (ref "D1") (pin "C") (pinfunction "C_C") (pintype "passive"))
      (node (ref "U$1") (pin "15") (pinfunction "VMB_15") (pintype "power_in"))
      (node (ref "U$1") (pin "28") (pinfunction "VMA_28") (pintype "power_in"))
      (node (ref "U$2") (pin "15") (pinfunction "VMB_15") (pintype "power_in"))
      (node (ref "U$2") (pin "28") (pinfunction "VMA_28") (pintype "power_in"))
      (node (ref "U$3") (pin "15") (pinfunction "VMB_15") (pintype "power_in"))
      (node (ref "U$3") (pin "28") (pinfunction "VMA_28") (pintype "power_in"))
      (node (ref "U$4") (pin "15") (pinfunction "VMB_15") (pintype "power_in"))
      (node (ref "U$4") (pin "28") (pinfunction "VMA_28") (pintype "power_in"))
    )
    (net (code "81") (name "unconnected-(SV1-Pad7)") (class "Default")
      (node (ref "SV1") (pin "7") (pinfunction "7_7") (pintype "passive"))
    )
    (net (code "82") (name "unconnected-(SV1-Pad10)") (class "Default")
      (node (ref "SV1") (pin "10") (pinfunction "10_10") (pintype "passive"))
    )
    (net (code "83") (name "unconnected-(SV1-Pad15)") (class "Default")
      (node (ref "SV1") (pin "15") (pinfunction "15_15") (pintype "passive"))
    )
    (net (code "84") (name "unconnected-(SV1-Pad18)") (class "Default")
      (node (ref "SV1") (pin "18") (pinfunction "18_18") (pintype "passive"))
    )
    (net (code "85") (name "unconnected-(U$1-HOME{slash}N-Pad2)") (class "Default")
      (node (ref "U$1") (pin "2") (pinfunction "HOME/N_2") (pintype "output"))
    )
    (net (code "86") (name "unconnected-(U$2-HOME{slash}N-Pad2)") (class "Default")
      (node (ref "U$2") (pin "2") (pinfunction "HOME/N_2") (pintype "output"))
    )
    (net (code "87") (name "unconnected-(U$3-HOME{slash}N-Pad2)") (class "Default")
      (node (ref "U$3") (pin "2") (pinfunction "HOME/N_2") (pintype "output"))
    )
    (net (code "88") (name "unconnected-(U$4-HOME{slash}N-Pad2)") (class "Default")
      (node (ref "U$4") (pin "2") (pinfunction "HOME/N_2") (pintype "output"))
    )
  )
)
